# midi11trigger.net
KiCad netlist of a schematic drawn in EAGLE
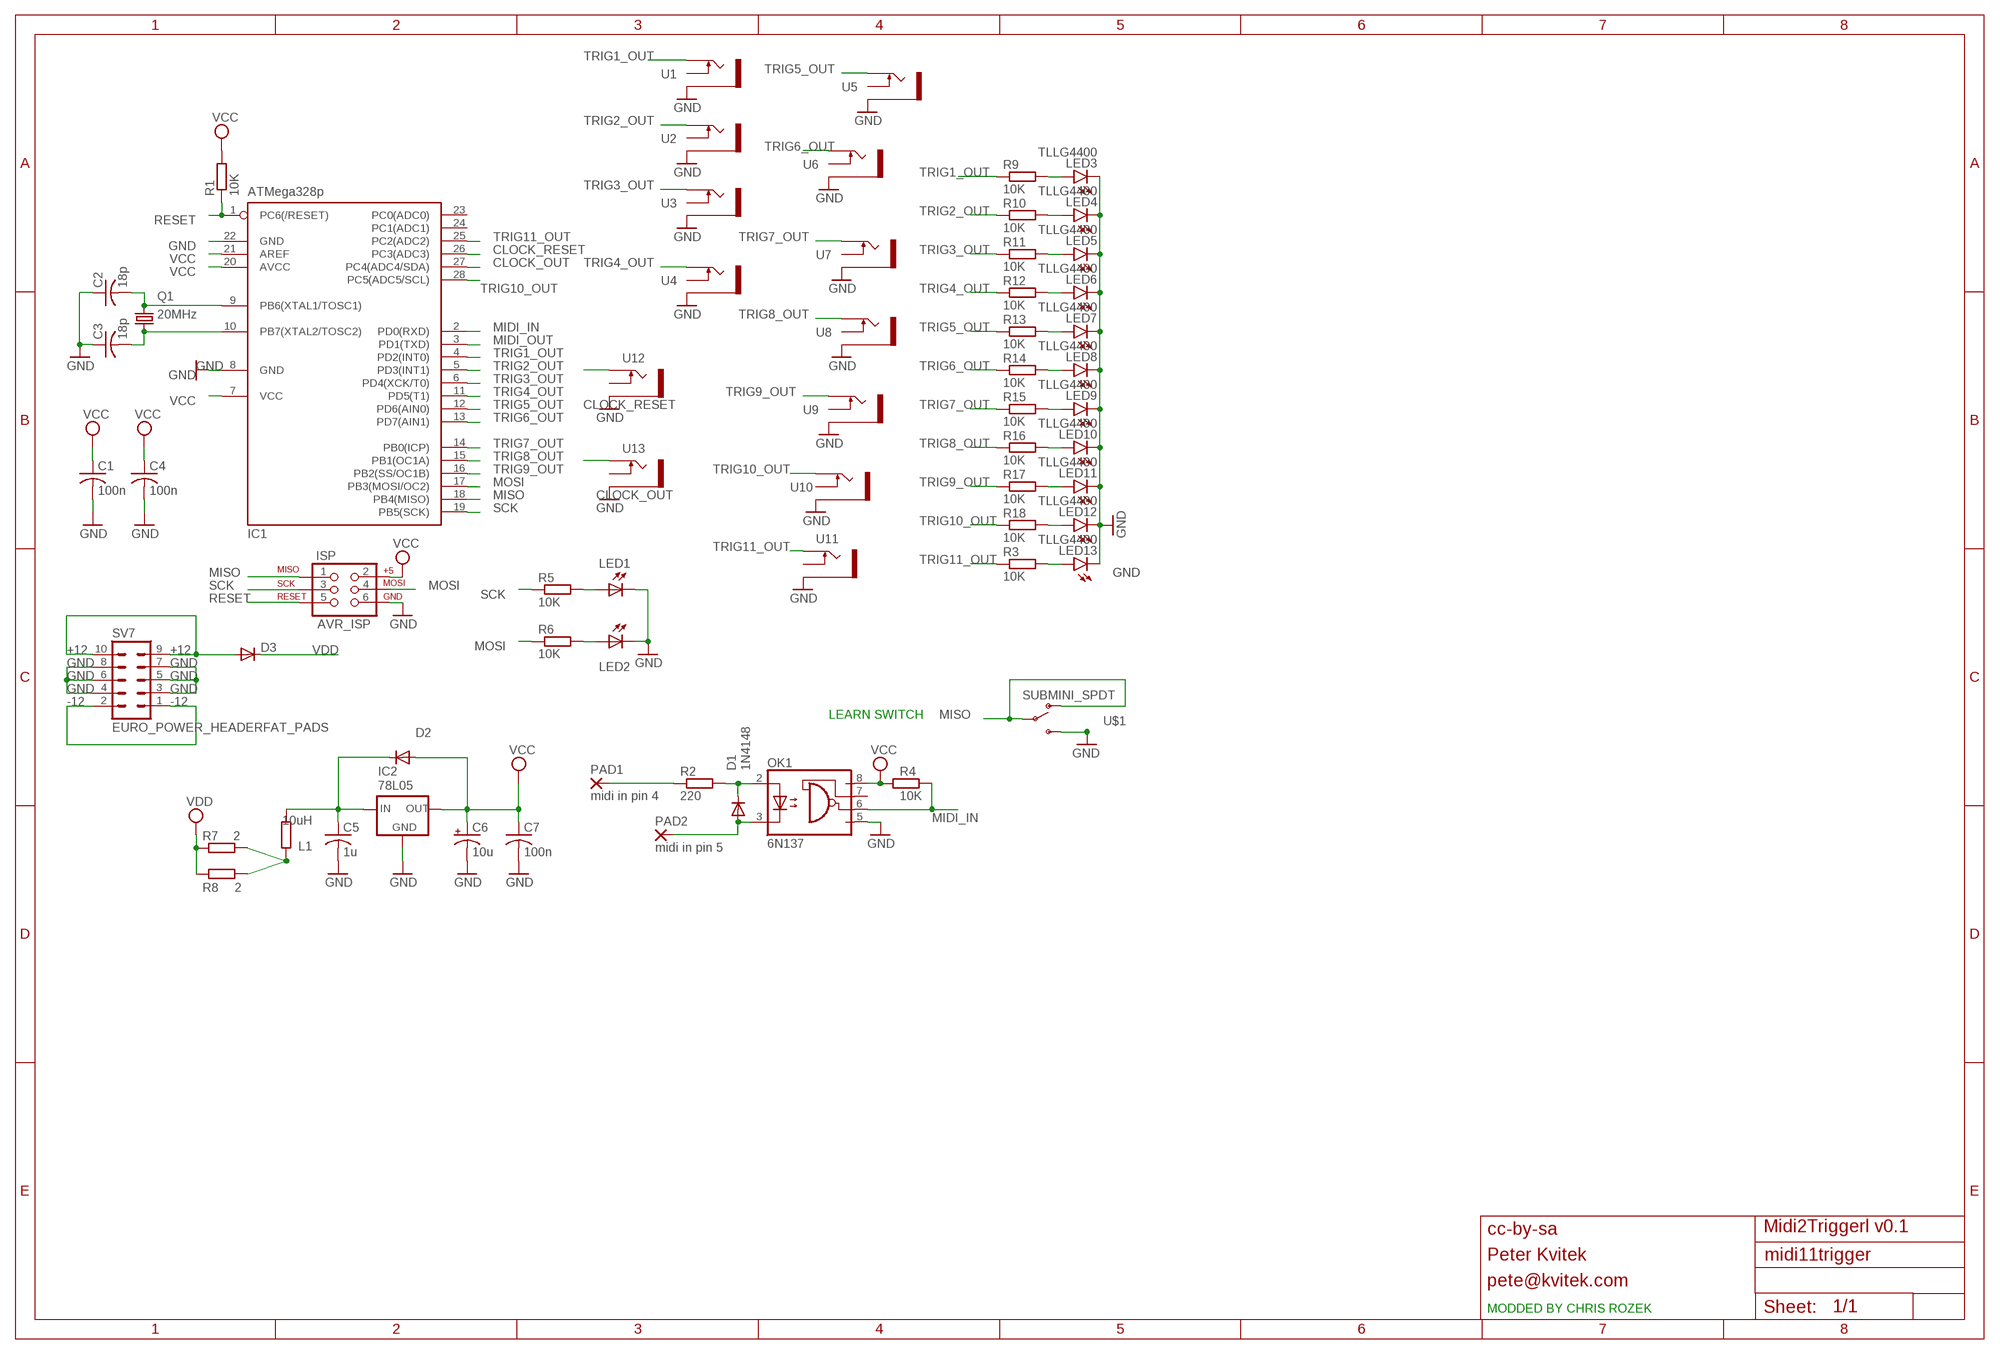
[diagram p0: schematic, sheet 1]

(export (version "E")
  (design (tool "Eeschema 10.0.6"))
  (components
    (comp (ref "C1")
      (value "100n")
      (footprint "eagle-import:C025-025X050")
      (libsource (lib "eagle-import") (part "C-US025-025X050"))
    )
    (comp (ref "C2")
      (value "18p")
      (footprint "eagle-import:C025-025X050")
      (libsource (lib "eagle-import") (part "C-US025-025X050"))
    )
    (comp (ref "C3")
      (value "18p")
      (footprint "eagle-import:C025-025X050")
      (libsource (lib "eagle-import") (part "C-US025-025X050"))
    )
    (comp (ref "C4")
      (value "100n")
      (footprint "eagle-import:C025-025X050")
      (libsource (lib "eagle-import") (part "C-US025-025X050"))
    )
    (comp (ref "C5")
      (value "1u")
      (footprint "eagle-import:C025-025X050")
      (libsource (lib "eagle-import") (part "C-US025-025X050"))
    )
    (comp (ref "C6")
      (value "10u")
      (footprint "eagle-import:E2,5-5")
      (libsource (lib "eagle-import") (part "CPOL-USE2.5-5"))
    )
    (comp (ref "C7")
      (value "100n")
      (footprint "eagle-import:C025-025X050")
      (libsource (lib "eagle-import") (part "C-US025-025X050"))
    )
    (comp (ref "D1")
      (value "1N4148")
      (footprint "eagle-import:DO35-7")
      (libsource (lib "eagle-import") (part "SMALL_DIODEDO35-7"))
    )
    (comp (ref "D2")
      (value "SMALL_DIODEDO35-7")
      (footprint "eagle-import:DO35-7")
      (libsource (lib "eagle-import") (part "SMALL_DIODEDO35-7"))
    )
    (comp (ref "D3")
      (value "SMALL_DIODEDO35-7")
      (footprint "eagle-import:DO35-7")
      (libsource (lib "eagle-import") (part "SMALL_DIODEDO35-7"))
    )
    (comp (ref "IC1")
      (value "ATMega328p")
      (footprint "eagle-import:DIL28-3")
      (libsource (lib "eagle-import") (part "MEGA8-P"))
    )
    (comp (ref "IC2")
      (value "78L05")
      (footprint "eagle-import:78LXX")
      (libsource (lib "eagle-import") (part "78LXX"))
    )
    (comp (ref "ISP")
      (value "AVR_ISP")
      (footprint "eagle-import:2X3")
      (libsource (lib "eagle-import") (part "AVR_SPI_PRG_6PTH"))
    )
    (comp (ref "L1")
      (value "10uH")
      (footprint "eagle-import:VERTICAL_RESISTOR")
      (libsource (lib "eagle-import") (part "RESISTORVERTICAL"))
    )
    (comp (ref "LED1")
      (value "LED3MM")
      (footprint "eagle-import:LED3MM")
      (libsource (lib "eagle-import") (part "LED3MM"))
    )
    (comp (ref "LED2")
      (value "LED3MM")
      (footprint "eagle-import:LED3MM")
      (libsource (lib "eagle-import") (part "LED3MM"))
    )
    (comp (ref "LED3")
      (value "TLLG4400")
      (footprint "eagle-import:LED3MM")
      (fields (field (name "MF") "VISHAY SEMICONDUCTOR"))
      (libsource (lib "eagle-import") (part "TLLG4400"))
    )
    (comp (ref "LED4")
      (value "TLLG4400")
      (footprint "eagle-import:LED3MM")
      (fields (field (name "MF") "VISHAY SEMICONDUCTOR"))
      (libsource (lib "eagle-import") (part "TLLG4400"))
    )
    (comp (ref "LED5")
      (value "TLLG4400")
      (footprint "eagle-import:LED3MM")
      (fields (field (name "MF") "VISHAY SEMICONDUCTOR"))
      (libsource (lib "eagle-import") (part "TLLG4400"))
    )
    (comp (ref "LED6")
      (value "TLLG4400")
      (footprint "eagle-import:LED3MM")
      (fields (field (name "MF") "VISHAY SEMICONDUCTOR"))
      (libsource (lib "eagle-import") (part "TLLG4400"))
    )
    (comp (ref "LED7")
      (value "TLLG4400")
      (footprint "eagle-import:LED3MM")
      (fields (field (name "MF") "VISHAY SEMICONDUCTOR"))
      (libsource (lib "eagle-import") (part "TLLG4400"))
    )
    (comp (ref "LED8")
      (value "TLLG4400")
      (footprint "eagle-import:LED3MM")
      (fields (field (name "MF") "VISHAY SEMICONDUCTOR"))
      (libsource (lib "eagle-import") (part "TLLG4400"))
    )
    (comp (ref "LED9")
      (value "TLLG4400")
      (footprint "eagle-import:LED3MM")
      (fields (field (name "MF") "VISHAY SEMICONDUCTOR"))
      (libsource (lib "eagle-import") (part "TLLG4400"))
    )
    (comp (ref "LED10")
      (value "TLLG4400")
      (footprint "eagle-import:LED3MM")
      (fields (field (name "MF") "VISHAY SEMICONDUCTOR"))
      (libsource (lib "eagle-import") (part "TLLG4400"))
    )
    (comp (ref "LED11")
      (value "TLLG4400")
      (footprint "eagle-import:LED3MM")
      (fields (field (name "MF") "VISHAY SEMICONDUCTOR"))
      (libsource (lib "eagle-import") (part "TLLG4400"))
    )
    (comp (ref "LED12")
      (value "TLLG4400")
      (footprint "eagle-import:LED3MM")
      (fields (field (name "MF") "VISHAY SEMICONDUCTOR"))
      (libsource (lib "eagle-import") (part "TLLG4400"))
    )
    (comp (ref "LED13")
      (value "TLLG4400")
      (footprint "eagle-import:LED3MM")
      (fields (field (name "MF") "VISHAY SEMICONDUCTOR"))
      (libsource (lib "eagle-import") (part "TLLG4400"))
    )
    (comp (ref "OK1")
      (value "6N137")
      (footprint "eagle-import:DIL08")
      (libsource (lib "eagle-import") (part "6N137"))
    )
    (comp (ref "PAD1")
      (value "midi in pin 4")
      (footprint "eagle-import:2,54_1,1")
      (libsource (lib "eagle-import") (part "2,54/1,1"))
    )
    (comp (ref "PAD2")
      (value "midi in pin 5")
      (footprint "eagle-import:2,54_1,1")
      (libsource (lib "eagle-import") (part "2,54/1,1"))
    )
    (comp (ref "Q1")
      (value "20MHz")
      (footprint "eagle-import:HC49U-V")
      (libsource (lib "eagle-import") (part "CRYSTALHC49U-V"))
    )
    (comp (ref "R1")
      (value "10K")
      (footprint "eagle-import:VERTICAL_RESISTOR")
      (libsource (lib "eagle-import") (part "RESISTORVERTICAL"))
    )
    (comp (ref "R2")
      (value "220")
      (footprint "eagle-import:VERTICAL_RESISTOR")
      (libsource (lib "eagle-import") (part "RESISTORVERTICAL"))
    )
    (comp (ref "R3")
      (value "10K")
      (footprint "eagle-import:VERTICAL_RESISTOR")
      (libsource (lib "eagle-import") (part "RESISTORVERTICAL"))
    )
    (comp (ref "R4")
      (value "10K")
      (footprint "eagle-import:VERTICAL_RESISTOR")
      (libsource (lib "eagle-import") (part "RESISTORVERTICAL"))
    )
    (comp (ref "R5")
      (value "10K")
      (footprint "eagle-import:VERTICAL_RESISTOR")
      (libsource (lib "eagle-import") (part "RESISTORVERTICAL"))
    )
    (comp (ref "R6")
      (value "10K")
      (footprint "eagle-import:VERTICAL_RESISTOR")
      (libsource (lib "eagle-import") (part "RESISTORVERTICAL"))
    )
    (comp (ref "R7")
      (value "2")
      (footprint "eagle-import:VERTICAL_RESISTOR")
      (libsource (lib "eagle-import") (part "RESISTORVERTICAL"))
    )
    (comp (ref "R8")
      (value "2")
      (footprint "eagle-import:VERTICAL_RESISTOR")
      (libsource (lib "eagle-import") (part "RESISTORVERTICAL"))
    )
    (comp (ref "R9")
      (value "10K")
      (footprint "eagle-import:VERTICAL_RESISTOR")
      (libsource (lib "eagle-import") (part "RESISTORVERTICAL"))
    )
    (comp (ref "R10")
      (value "10K")
      (footprint "eagle-import:VERTICAL_RESISTOR")
      (libsource (lib "eagle-import") (part "RESISTORVERTICAL"))
    )
    (comp (ref "R11")
      (value "10K")
      (footprint "eagle-import:VERTICAL_RESISTOR")
      (libsource (lib "eagle-import") (part "RESISTORVERTICAL"))
    )
    (comp (ref "R12")
      (value "10K")
      (footprint "eagle-import:VERTICAL_RESISTOR")
      (libsource (lib "eagle-import") (part "RESISTORVERTICAL"))
    )
    (comp (ref "R13")
      (value "10K")
      (footprint "eagle-import:VERTICAL_RESISTOR")
      (libsource (lib "eagle-import") (part "RESISTORVERTICAL"))
    )
    (comp (ref "R14")
      (value "10K")
      (footprint "eagle-import:VERTICAL_RESISTOR")
      (libsource (lib "eagle-import") (part "RESISTORVERTICAL"))
    )
    (comp (ref "R15")
      (value "10K")
      (footprint "eagle-import:VERTICAL_RESISTOR")
      (libsource (lib "eagle-import") (part "RESISTORVERTICAL"))
    )
    (comp (ref "R16")
      (value "10K")
      (footprint "eagle-import:VERTICAL_RESISTOR")
      (libsource (lib "eagle-import") (part "RESISTORVERTICAL"))
    )
    (comp (ref "R17")
      (value "10K")
      (footprint "eagle-import:VERTICAL_RESISTOR")
      (libsource (lib "eagle-import") (part "RESISTORVERTICAL"))
    )
    (comp (ref "R18")
      (value "10K")
      (footprint "eagle-import:VERTICAL_RESISTOR")
      (libsource (lib "eagle-import") (part "RESISTORVERTICAL"))
    )
    (comp (ref "SV7")
      (value "EURO_POWER_HEADERFAT_PADS")
      (footprint "eagle-import:EURO_PWR_HEADER_FAT")
      (libsource (lib "eagle-import") (part "EURO_POWER_HEADERFAT_PADS"))
    )
    (comp (ref "U$1")
      (value "SUBMINI_SPDT")
      (footprint "eagle-import:SUBMINI_TOGGLE")
      (libsource (lib "eagle-import") (part "SUBMINI_SPDT"))
    )
    (comp (ref "U1")
      (value "THONKICONNNEW")
      (footprint "eagle-import:WQP-PJ301M-12_JACK")
      (libsource (lib "eagle-import") (part "THONKICONNNEW"))
    )
    (comp (ref "U2")
      (value "THONKICONNNEW")
      (footprint "eagle-import:WQP-PJ301M-12_JACK")
      (libsource (lib "eagle-import") (part "THONKICONNNEW"))
    )
    (comp (ref "U3")
      (value "THONKICONNNEW")
      (footprint "eagle-import:WQP-PJ301M-12_JACK")
      (libsource (lib "eagle-import") (part "THONKICONNNEW"))
    )
    (comp (ref "U4")
      (value "THONKICONNNEW")
      (footprint "eagle-import:WQP-PJ301M-12_JACK")
      (libsource (lib "eagle-import") (part "THONKICONNNEW"))
    )
    (comp (ref "U5")
      (value "THONKICONNNEW")
      (footprint "eagle-import:WQP-PJ301M-12_JACK")
      (libsource (lib "eagle-import") (part "THONKICONNNEW"))
    )
    (comp (ref "U6")
      (value "THONKICONNNEW")
      (footprint "eagle-import:WQP-PJ301M-12_JACK")
      (libsource (lib "eagle-import") (part "THONKICONNNEW"))
    )
    (comp (ref "U7")
      (value "THONKICONNNEW")
      (footprint "eagle-import:WQP-PJ301M-12_JACK")
      (libsource (lib "eagle-import") (part "THONKICONNNEW"))
    )
    (comp (ref "U8")
      (value "THONKICONNNEW")
      (footprint "eagle-import:WQP-PJ301M-12_JACK")
      (libsource (lib "eagle-import") (part "THONKICONNNEW"))
    )
    (comp (ref "U9")
      (value "THONKICONNNEW")
      (footprint "eagle-import:WQP-PJ301M-12_JACK")
      (libsource (lib "eagle-import") (part "THONKICONNNEW"))
    )
    (comp (ref "U10")
      (value "THONKICONNNEW")
      (footprint "eagle-import:WQP-PJ301M-12_JACK")
      (libsource (lib "eagle-import") (part "THONKICONNNEW"))
    )
    (comp (ref "U11")
      (value "THONKICONNNEW")
      (footprint "eagle-import:WQP-PJ301M-12_JACK")
      (libsource (lib "eagle-import") (part "THONKICONNNEW"))
    )
    (comp (ref "U12")
      (value "THONKICONNNEW")
      (footprint "eagle-import:WQP-PJ301M-12_JACK")
      (libsource (lib "eagle-import") (part "THONKICONNNEW"))
    )
    (comp (ref "U13")
      (value "THONKICONNNEW")
      (footprint "eagle-import:WQP-PJ301M-12_JACK")
      (libsource (lib "eagle-import") (part "THONKICONNNEW"))
    )
  )
  (nets
    (net (code "1") (name "/+12") (class "Default")
      (node (ref "D3") (pin "A") (pinfunction "A_A") (pintype "passive"))
      (node (ref "SV7") (pin "10") (pinfunction "10_10") (pintype "passive"))
      (node (ref "SV7") (pin "9") (pinfunction "9_9") (pintype "passive"))
    )
    (net (code "2") (name "/-12") (class "Default")
      (node (ref "SV7") (pin "1") (pinfunction "1_1") (pintype "passive"))
      (node (ref "SV7") (pin "2") (pinfunction "2_2") (pintype "passive"))
    )
    (net (code "3") (name "/CLOCK_OUT") (class "Default")
      (node (ref "IC1") (pin "27") (pinfunction "PC4(ADC4/SDA)_27") (pintype "bidirectional"))
      (node (ref "U13") (pin "P$1_TIP") (pinfunction "TIP_P$1_TIP") (pintype "passive"))
    )
    (net (code "4") (name "/CLOCK_RESET") (class "Default")
      (node (ref "IC1") (pin "26") (pinfunction "PC3(ADC3)_26") (pintype "bidirectional"))
      (node (ref "U12") (pin "P$1_TIP") (pinfunction "TIP_P$1_TIP") (pintype "passive"))
    )
    (net (code "5") (name "/MIDI_IN") (class "Default")
      (node (ref "IC1") (pin "2") (pinfunction "PD0(RXD)_2") (pintype "bidirectional"))
      (node (ref "OK1") (pin "6") (pinfunction "VO_6") (pintype "passive"))
      (node (ref "R4") (pin "2") (pinfunction "2_2") (pintype "passive"))
    )
    (net (code "6") (name "/MIDI_OUT") (class "Default")
      (node (ref "IC1") (pin "3") (pinfunction "PD1(TXD)_3") (pintype "bidirectional"))
    )
    (net (code "7") (name "/MISO") (class "Default")
      (node (ref "IC1") (pin "18") (pinfunction "PB4(MISO)_18") (pintype "bidirectional"))
      (node (ref "ISP") (pin "1") (pinfunction "1_1") (pintype "passive"))
      (node (ref "U$1") (pin "1") (pinfunction "O_1") (pintype "passive"))
      (node (ref "U$1") (pin "COM") (pinfunction "COMMON_COM") (pintype "passive"))
    )
    (net (code "8") (name "/MOSI") (class "Default")
      (node (ref "IC1") (pin "17") (pinfunction "PB3(MOSI/OC2)_17") (pintype "bidirectional"))
      (node (ref "ISP") (pin "4") (pinfunction "4_4") (pintype "passive"))
      (node (ref "R6") (pin "1") (pinfunction "1_1") (pintype "passive"))
    )
    (net (code "9") (name "/RESET") (class "Default")
      (node (ref "IC1") (pin "1") (pinfunction "PC6(/RESET)_1") (pintype "bidirectional"))
      (node (ref "ISP") (pin "5") (pinfunction "5_5") (pintype "passive"))
      (node (ref "R1") (pin "1") (pinfunction "1_1") (pintype "passive"))
    )
    (net (code "10") (name "/SCK") (class "Default")
      (node (ref "IC1") (pin "19") (pinfunction "PB5(SCK)_19") (pintype "bidirectional"))
      (node (ref "ISP") (pin "3") (pinfunction "3_3") (pintype "passive"))
      (node (ref "R5") (pin "1") (pinfunction "1_1") (pintype "passive"))
    )
    (net (code "11") (name "/TRIG1_OUT") (class "Default")
      (node (ref "IC1") (pin "4") (pinfunction "PD2(INT0)_4") (pintype "bidirectional"))
      (node (ref "R9") (pin "1") (pinfunction "1_1") (pintype "passive"))
      (node (ref "U1") (pin "P$1_TIP") (pinfunction "TIP_P$1_TIP") (pintype "passive"))
    )
    (net (code "12") (name "/TRIG2_OUT") (class "Default")
      (node (ref "IC1") (pin "5") (pinfunction "PD3(INT1)_5") (pintype "bidirectional"))
      (node (ref "R10") (pin "1") (pinfunction "1_1") (pintype "passive"))
      (node (ref "U2") (pin "P$1_TIP") (pinfunction "TIP_P$1_TIP") (pintype "passive"))
    )
    (net (code "13") (name "/TRIG3_OUT") (class "Default")
      (node (ref "IC1") (pin "6") (pinfunction "PD4(XCK/T0)_6") (pintype "bidirectional"))
      (node (ref "R11") (pin "1") (pinfunction "1_1") (pintype "passive"))
      (node (ref "U3") (pin "P$1_TIP") (pinfunction "TIP_P$1_TIP") (pintype "passive"))
    )
    (net (code "14") (name "/TRIG4_OUT") (class "Default")
      (node (ref "IC1") (pin "11") (pinfunction "PD5(T1)_11") (pintype "bidirectional"))
      (node (ref "R12") (pin "1") (pinfunction "1_1") (pintype "passive"))
      (node (ref "U4") (pin "P$1_TIP") (pinfunction "TIP_P$1_TIP") (pintype "passive"))
    )
    (net (code "15") (name "/TRIG5_OUT") (class "Default")
      (node (ref "IC1") (pin "12") (pinfunction "PD6(AIN0)_12") (pintype "bidirectional"))
      (node (ref "R13") (pin "1") (pinfunction "1_1") (pintype "passive"))
      (node (ref "U5") (pin "P$1_TIP") (pinfunction "TIP_P$1_TIP") (pintype "passive"))
    )
    (net (code "16") (name "/TRIG6_OUT") (class "Default")
      (node (ref "IC1") (pin "13") (pinfunction "PD7(AIN1)_13") (pintype "bidirectional"))
      (node (ref "R14") (pin "1") (pinfunction "1_1") (pintype "passive"))
      (node (ref "U6") (pin "P$1_TIP") (pinfunction "TIP_P$1_TIP") (pintype "passive"))
    )
    (net (code "17") (name "/TRIG7_OUT") (class "Default")
      (node (ref "IC1") (pin "14") (pinfunction "PB0(ICP)_14") (pintype "bidirectional"))
      (node (ref "R15") (pin "1") (pinfunction "1_1") (pintype "passive"))
      (node (ref "U7") (pin "P$1_TIP") (pinfunction "TIP_P$1_TIP") (pintype "passive"))
    )
    (net (code "18") (name "/TRIG8_OUT") (class "Default")
      (node (ref "IC1") (pin "15") (pinfunction "PB1(OC1A)_15") (pintype "bidirectional"))
      (node (ref "R16") (pin "1") (pinfunction "1_1") (pintype "passive"))
      (node (ref "U8") (pin "P$1_TIP") (pinfunction "TIP_P$1_TIP") (pintype "passive"))
    )
    (net (code "19") (name "/TRIG9_OUT") (class "Default")
      (node (ref "IC1") (pin "16") (pinfunction "PB2(SS/OC1B)_16") (pintype "bidirectional"))
      (node (ref "R17") (pin "1") (pinfunction "1_1") (pintype "passive"))
      (node (ref "U9") (pin "P$1_TIP") (pinfunction "TIP_P$1_TIP") (pintype "passive"))
    )
    (net (code "20") (name "/TRIG10_OUT") (class "Default")
      (node (ref "IC1") (pin "28") (pinfunction "PC5(ADC5/SCL)_28") (pintype "bidirectional"))
      (node (ref "R18") (pin "1") (pinfunction "1_1") (pintype "passive"))
      (node (ref "U10") (pin "P$1_TIP") (pinfunction "TIP_P$1_TIP") (pintype "passive"))
    )
    (net (code "21") (name "/TRIG11_OUT") (class "Default")
      (node (ref "IC1") (pin "25") (pinfunction "PC2(ADC2)_25") (pintype "bidirectional"))
      (node (ref "R3") (pin "1") (pinfunction "1_1") (pintype "passive"))
      (node (ref "U11") (pin "P$1_TIP") (pinfunction "TIP_P$1_TIP") (pintype "passive"))
    )
    (net (code "22") (name "GND") (class "Default")
      (node (ref "C1") (pin "2") (pinfunction "2_2") (pintype "passive"))
      (node (ref "C2") (pin "1") (pinfunction "1_1") (pintype "passive"))
      (node (ref "C3") (pin "1") (pinfunction "1_1") (pintype "passive"))
      (node (ref "C4") (pin "2") (pinfunction "2_2") (pintype "passive"))
      (node (ref "C5") (pin "2") (pinfunction "2_2") (pintype "passive"))
      (node (ref "C6") (pin "-") (pinfunction "-_-") (pintype "passive"))
      (node (ref "C7") (pin "2") (pinfunction "2_2") (pintype "passive"))
      (node (ref "IC1") (pin "22") (pinfunction "GND_22") (pintype "power_in"))
      (node (ref "IC1") (pin "8") (pinfunction "GND_8") (pintype "power_in"))
      (node (ref "IC2") (pin "GND") (pinfunction "GND_GND") (pintype "input"))
      (node (ref "ISP") (pin "6") (pinfunction "6_6") (pintype "passive"))
      (node (ref "LED1") (pin "K") (pinfunction "C_K") (pintype "passive"))
      (node (ref "LED10") (pin "K") (pinfunction "C_K") (pintype "passive"))
      (node (ref "LED11") (pin "K") (pinfunction "C_K") (pintype "passive"))
      (node (ref "LED12") (pin "K") (pinfunction "C_K") (pintype "passive"))
      (node (ref "LED13") (pin "K") (pinfunction "C_K") (pintype "passive"))
      (node (ref "LED2") (pin "K") (pinfunction "C_K") (pintype "passive"))
      (node (ref "LED3") (pin "K") (pinfunction "C_K") (pintype "passive"))
      (node (ref "LED4") (pin "K") (pinfunction "C_K") (pintype "passive"))
      (node (ref "LED5") (pin "K") (pinfunction "C_K") (pintype "passive"))
      (node (ref "LED6") (pin "K") (pinfunction "C_K") (pintype "passive"))
      (node (ref "LED7") (pin "K") (pinfunction "C_K") (pintype "passive"))
      (node (ref "LED8") (pin "K") (pinfunction "C_K") (pintype "passive"))
      (node (ref "LED9") (pin "K") (pinfunction "C_K") (pintype "passive"))
      (node (ref "OK1") (pin "5") (pinfunction "GND_5") (pintype "passive"))
      (node (ref "SV7") (pin "3") (pinfunction "3_3") (pintype "passive"))
      (node (ref "SV7") (pin "4") (pinfunction "4_4") (pintype "passive"))
      (node (ref "SV7") (pin "5") (pinfunction "5_5") (pintype "passive"))
      (node (ref "SV7") (pin "6") (pinfunction "6_6") (pintype "passive"))
      (node (ref "SV7") (pin "7") (pinfunction "7_7") (pintype "passive"))
      (node (ref "SV7") (pin "8") (pinfunction "8_8") (pintype "passive"))
      (node (ref "U$1") (pin "3") (pinfunction "S_3") (pintype "passive"))
      (node (ref "U1") (pin "P$3_SLEEVE") (pinfunction "SLEEVE_P$3_SLEEVE") (pintype "passive"))
      (node (ref "U10") (pin "P$3_SLEEVE") (pinfunction "SLEEVE_P$3_SLEEVE") (pintype "passive"))
      (node (ref "U11") (pin "P$3_SLEEVE") (pinfunction "SLEEVE_P$3_SLEEVE") (pintype "passive"))
      (node (ref "U12") (pin "P$3_SLEEVE") (pinfunction "SLEEVE_P$3_SLEEVE") (pintype "passive"))
      (node (ref "U13") (pin "P$3_SLEEVE") (pinfunction "SLEEVE_P$3_SLEEVE") (pintype "passive"))
      (node (ref "U2") (pin "P$3_SLEEVE") (pinfunction "SLEEVE_P$3_SLEEVE") (pintype "passive"))
      (node (ref "U3") (pin "P$3_SLEEVE") (pinfunction "SLEEVE_P$3_SLEEVE") (pintype "passive"))
      (node (ref "U4") (pin "P$3_SLEEVE") (pinfunction "SLEEVE_P$3_SLEEVE") (pintype "passive"))
      (node (ref "U5") (pin "P$3_SLEEVE") (pinfunction "SLEEVE_P$3_SLEEVE") (pintype "passive"))
      (node (ref "U6") (pin "P$3_SLEEVE") (pinfunction "SLEEVE_P$3_SLEEVE") (pintype "passive"))
      (node (ref "U7") (pin "P$3_SLEEVE") (pinfunction "SLEEVE_P$3_SLEEVE") (pintype "passive"))
      (node (ref "U8") (pin "P$3_SLEEVE") (pinfunction "SLEEVE_P$3_SLEEVE") (pintype "passive"))
      (node (ref "U9") (pin "P$3_SLEEVE") (pinfunction "SLEEVE_P$3_SLEEVE") (pintype "passive"))
    )
    (net (code "23") (name "Net-(C5-Pad1)") (class "Default")
      (node (ref "C5") (pin "1") (pinfunction "1_1") (pintype "passive"))
      (node (ref "D2") (pin "C") (pinfunction "C_C") (pintype "passive"))
      (node (ref "IC2") (pin "IN") (pinfunction "IN_IN") (pintype "input"))
      (node (ref "L1") (pin "2") (pinfunction "2_2") (pintype "passive"))
    )
    (net (code "24") (name "Net-(IC1-PB6(XTAL1{slash}TOSC1))") (class "Default")
      (node (ref "C2") (pin "2") (pinfunction "2_2") (pintype "passive"))
      (node (ref "IC1") (pin "9") (pinfunction "PB6(XTAL1/TOSC1)_9") (pintype "bidirectional"))
      (node (ref "Q1") (pin "2") (pinfunction "2_2") (pintype "passive"))
    )
    (net (code "25") (name "Net-(IC1-PB7(XTAL2{slash}TOSC2))") (class "Default")
      (node (ref "C3") (pin "2") (pinfunction "2_2") (pintype "passive"))
      (node (ref "IC1") (pin "10") (pinfunction "PB7(XTAL2/TOSC2)_10") (pintype "bidirectional"))
      (node (ref "Q1") (pin "1") (pinfunction "1_1") (pintype "passive"))
    )
    (net (code "26") (name "Net-(L1-Pad1)") (class "Default")
      (node (ref "L1") (pin "1") (pinfunction "1_1") (pintype "passive"))
      (node (ref "R7") (pin "2") (pinfunction "2_2") (pintype "passive"))
      (node (ref "R8") (pin "2") (pinfunction "2_2") (pintype "passive"))
    )
    (net (code "27") (name "Net-(LED1-PadA)") (class "Default")
      (node (ref "LED1") (pin "A") (pinfunction "A_A") (pintype "passive"))
      (node (ref "R5") (pin "2") (pinfunction "2_2") (pintype "passive"))
    )
    (net (code "28") (name "Net-(LED2-PadA)") (class "Default")
      (node (ref "LED2") (pin "A") (pinfunction "A_A") (pintype "passive"))
      (node (ref "R6") (pin "2") (pinfunction "2_2") (pintype "passive"))
    )
    (net (code "29") (name "Net-(LED3-PadA)") (class "Default")
      (node (ref "LED3") (pin "A") (pinfunction "A_A") (pintype "passive"))
      (node (ref "R9") (pin "2") (pinfunction "2_2") (pintype "passive"))
    )
    (net (code "30") (name "Net-(LED4-PadA)") (class "Default")
      (node (ref "LED4") (pin "A") (pinfunction "A_A") (pintype "passive"))
      (node (ref "R10") (pin "2") (pinfunction "2_2") (pintype "passive"))
    )
    (net (code "31") (name "Net-(LED5-PadA)") (class "Default")
      (node (ref "LED5") (pin "A") (pinfunction "A_A") (pintype "passive"))
      (node (ref "R11") (pin "2") (pinfunction "2_2") (pintype "passive"))
    )
    (net (code "32") (name "Net-(LED6-PadA)") (class "Default")
      (node (ref "LED6") (pin "A") (pinfunction "A_A") (pintype "passive"))
      (node (ref "R12") (pin "2") (pinfunction "2_2") (pintype "passive"))
    )
    (net (code "33") (name "Net-(LED7-PadA)") (class "Default")
      (node (ref "LED7") (pin "A") (pinfunction "A_A") (pintype "passive"))
      (node (ref "R13") (pin "2") (pinfunction "2_2") (pintype "passive"))
    )
    (net (code "34") (name "Net-(LED8-PadA)") (class "Default")
      (node (ref "LED8") (pin "A") (pinfunction "A_A") (pintype "passive"))
      (node (ref "R14") (pin "2") (pinfunction "2_2") (pintype "passive"))
    )
    (net (code "35") (name "Net-(LED9-PadA)") (class "Default")
      (node (ref "LED9") (pin "A") (pinfunction "A_A") (pintype "passive"))
      (node (ref "R15") (pin "2") (pinfunction "2_2") (pintype "passive"))
    )
    (net (code "36") (name "Net-(LED10-PadA)") (class "Default")
      (node (ref "LED10") (pin "A") (pinfunction "A_A") (pintype "passive"))
      (node (ref "R16") (pin "2") (pinfunction "2_2") (pintype "passive"))
    )
    (net (code "37") (name "Net-(LED11-PadA)") (class "Default")
      (node (ref "LED11") (pin "A") (pinfunction "A_A") (pintype "passive"))
      (node (ref "R17") (pin "2") (pinfunction "2_2") (pintype "passive"))
    )
    (net (code "38") (name "Net-(LED12-PadA)") (class "Default")
      (node (ref "LED12") (pin "A") (pinfunction "A_A") (pintype "passive"))
      (node (ref "R18") (pin "2") (pinfunction "2_2") (pintype "passive"))
    )
    (net (code "39") (name "Net-(LED13-PadA)") (class "Default")
      (node (ref "LED13") (pin "A") (pinfunction "A_A") (pintype "passive"))
      (node (ref "R3") (pin "2") (pinfunction "2_2") (pintype "passive"))
    )
    (net (code "40") (name "Net-(OK1-A)") (class "Default")
      (node (ref "D1") (pin "C") (pinfunction "C_C") (pintype "passive"))
      (node (ref "OK1") (pin "2") (pinfunction "A_2") (pintype "passive"))
      (node (ref "R2") (pin "2") (pinfunction "2_2") (pintype "passive"))
    )
    (net (code "41") (name "Net-(OK1-C)") (class "Default")
      (node (ref "D1") (pin "A") (pinfunction "A_A") (pintype "passive"))
      (node (ref "OK1") (pin "3") (pinfunction "C_3") (pintype "passive"))
      (node (ref "PAD2") (pin "1") (pinfunction "P_1") (pintype "passive"))
    )
    (net (code "42") (name "Net-(PAD1-P)") (class "Default")
      (node (ref "PAD1") (pin "1") (pinfunction "P_1") (pintype "passive"))
      (node (ref "R2") (pin "1") (pinfunction "1_1") (pintype "passive"))
    )
    (net (code "43") (name "VCC") (class "Default")
      (node (ref "C1") (pin "1") (pinfunction "1_1") (pintype "passive"))
      (node (ref "C4") (pin "1") (pinfunction "1_1") (pintype "passive"))
      (node (ref "C6") (pin "+") (pinfunction "+_+") (pintype "passive"))
      (node (ref "C7") (pin "1") (pinfunction "1_1") (pintype "passive"))
      (node (ref "D2") (pin "A") (pinfunction "A_A") (pintype "passive"))
      (node (ref "IC1") (pin "20") (pinfunction "AVCC_20") (pintype "power_in"))
      (node (ref "IC1") (pin "21") (pinfunction "AREF_21") (pintype "passive"))
      (node (ref "IC1") (pin "7") (pinfunction "VCC_7") (pintype "power_in"))
      (node (ref "IC2") (pin "OUT") (pinfunction "OUT_OUT") (pintype "passive"))
      (node (ref "ISP") (pin "2") (pinfunction "2_2") (pintype "passive"))
      (node (ref "OK1") (pin "8") (pinfunction "VCC_8") (pintype "passive"))
      (node (ref "R1") (pin "2") (pinfunction "2_2") (pintype "passive"))
      (node (ref "R4") (pin "1") (pinfunction "1_1") (pintype "passive"))
    )
    (net (code "44") (name "VDD") (class "Default")
      (node (ref "D3") (pin "C") (pinfunction "C_C") (pintype "passive"))
      (node (ref "R7") (pin "1") (pinfunction "1_1") (pintype "passive"))
      (node (ref "R8") (pin "1") (pinfunction "1_1") (pintype "passive"))
    )
    (net (code "45") (name "unconnected-(IC1-PC0(ADC0)-Pad23)") (class "Default")
      (node (ref "IC1") (pin "23") (pinfunction "PC0(ADC0)_23") (pintype "bidirectional"))
    )
    (net (code "46") (name "unconnected-(IC1-PC1(ADC1)-Pad24)") (class "Default")
      (node (ref "IC1") (pin "24") (pinfunction "PC1(ADC1)_24") (pintype "bidirectional"))
    )
    (net (code "47") (name "unconnected-(OK1-VE-Pad7)") (class "Default")
      (node (ref "OK1") (pin "7") (pinfunction "VE_7") (pintype "passive"))
    )
    (net (code "48") (name "unconnected-(U1-SWITCH-PadP$2_SWITCH)") (class "Default")
      (node (ref "U1") (pin "P$2_SWITCH") (pinfunction "SWITCH_P$2_SWITCH") (pintype "passive"))
    )
    (net (code "49") (name "unconnected-(U2-SWITCH-PadP$2_SWITCH)") (class "Default")
      (node (ref "U2") (pin "P$2_SWITCH") (pinfunction "SWITCH_P$2_SWITCH") (pintype "passive"))
    )
    (net (code "50") (name "unconnected-(U3-SWITCH-PadP$2_SWITCH)") (class "Default")
      (node (ref "U3") (pin "P$2_SWITCH") (pinfunction "SWITCH_P$2_SWITCH") (pintype "passive"))
    )
    (net (code "51") (name "unconnected-(U4-SWITCH-PadP$2_SWITCH)") (class "Default")
      (node (ref "U4") (pin "P$2_SWITCH") (pinfunction "SWITCH_P$2_SWITCH") (pintype "passive"))
    )
    (net (code "52") (name "unconnected-(U5-SWITCH-PadP$2_SWITCH)") (class "Default")
      (node (ref "U5") (pin "P$2_SWITCH") (pinfunction "SWITCH_P$2_SWITCH") (pintype "passive"))
    )
    (net (code "53") (name "unconnected-(U6-SWITCH-PadP$2_SWITCH)") (class "Default")
      (node (ref "U6") (pin "P$2_SWITCH") (pinfunction "SWITCH_P$2_SWITCH") (pintype "passive"))
    )
    (net (code "54") (name "unconnected-(U7-SWITCH-PadP$2_SWITCH)") (class "Default")
      (node (ref "U7") (pin "P$2_SWITCH") (pinfunction "SWITCH_P$2_SWITCH") (pintype "passive"))
    )
    (net (code "55") (name "unconnected-(U8-SWITCH-PadP$2_SWITCH)") (class "Default")
      (node (ref "U8") (pin "P$2_SWITCH") (pinfunction "SWITCH_P$2_SWITCH") (pintype "passive"))
    )
    (net (code "56") (name "unconnected-(U9-SWITCH-PadP$2_SWITCH)") (class "Default")
      (node (ref "U9") (pin "P$2_SWITCH") (pinfunction "SWITCH_P$2_SWITCH") (pintype "passive"))
    )
    (net (code "57") (name "unconnected-(U10-SWITCH-PadP$2_SWITCH)") (class "Default")
      (node (ref "U10") (pin "P$2_SWITCH") (pinfunction "SWITCH_P$2_SWITCH") (pintype "passive"))
    )
    (net (code "58") (name "unconnected-(U11-SWITCH-PadP$2_SWITCH)") (class "Default")
      (node (ref "U11") (pin "P$2_SWITCH") (pinfunction "SWITCH_P$2_SWITCH") (pintype "passive"))
    )
    (net (code "59") (name "unconnected-(U12-SWITCH-PadP$2_SWITCH)") (class "Default")
      (node (ref "U12") (pin "P$2_SWITCH") (pinfunction "SWITCH_P$2_SWITCH") (pintype "passive"))
    )
    (net (code "60") (name "unconnected-(U13-SWITCH-PadP$2_SWITCH)") (class "Default")
      (node (ref "U13") (pin "P$2_SWITCH") (pinfunction "SWITCH_P$2_SWITCH") (pintype "passive"))
    )
  )
)
